# proto.net
KiCad netlist of a schematic drawn in EAGLE
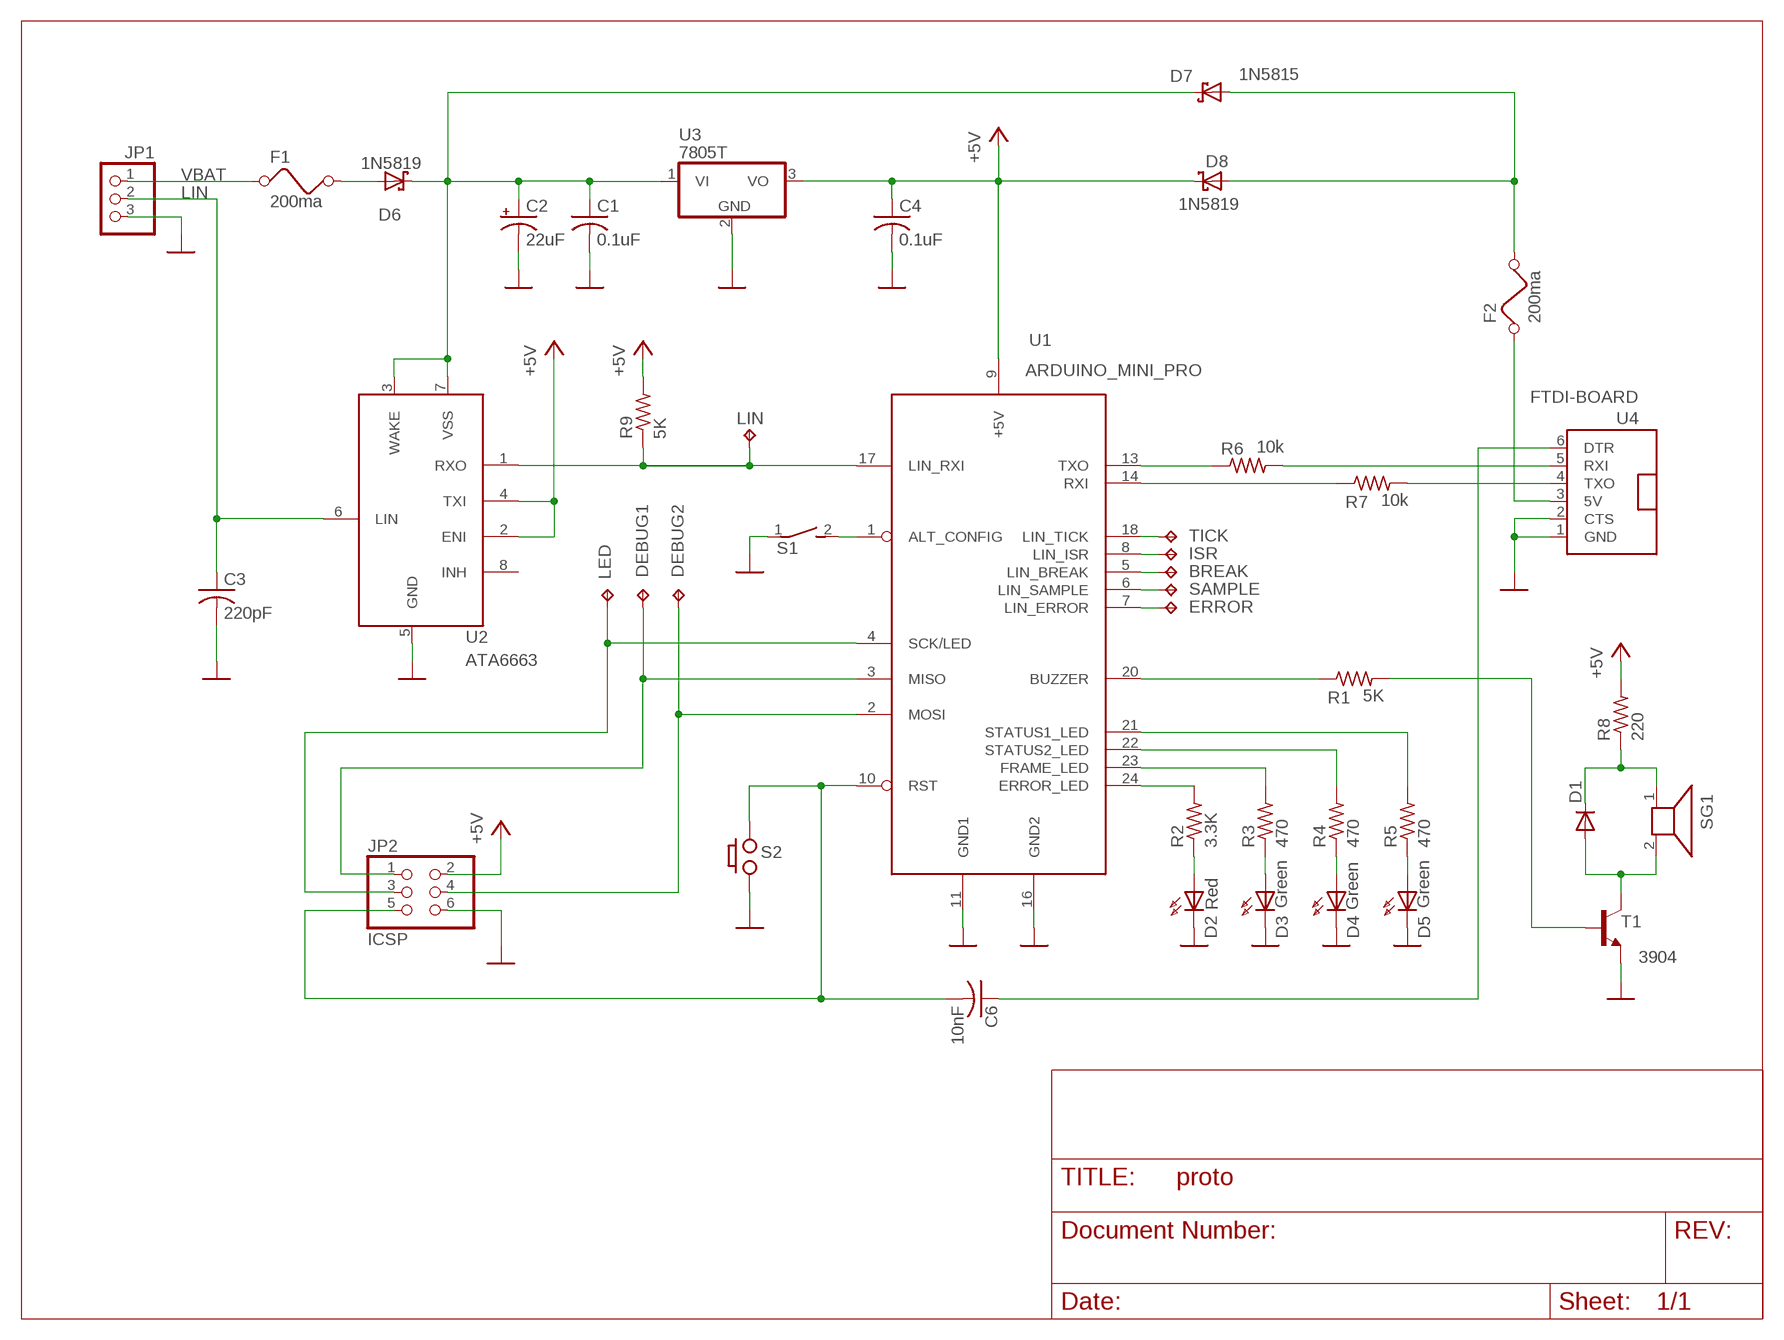
[diagram p0: schematic, sheet 1]

(export (version "E")
  (design (tool "Eeschema 10.0.6"))
  (components
    (comp (ref "BREAK")
      (value "TPPAD1-17")
      (footprint "eagle-import:P1-17")
      (libsource (lib "eagle-import") (part "TPPAD1-17"))
    )
    (comp (ref "C1")
      (value "0.1uF")
      (footprint "eagle-import:C0805")
      (libsource (lib "eagle-import") (part "C-USC0805"))
    )
    (comp (ref "C2")
      (value "22uF")
      (footprint "eagle-import:SMC_C")
      (libsource (lib "eagle-import") (part "CPOL-USSMCC"))
    )
    (comp (ref "C3")
      (value "220pF")
      (footprint "eagle-import:C0805")
      (libsource (lib "eagle-import") (part "C-USC0805"))
    )
    (comp (ref "C4")
      (value "0.1uF")
      (footprint "eagle-import:C0805")
      (libsource (lib "eagle-import") (part "C-USC0805"))
    )
    (comp (ref "C6")
      (value "10nF")
      (footprint "eagle-import:C0805")
      (libsource (lib "eagle-import") (part "C-USC0805"))
    )
    (comp (ref "D1")
      (value "DIODE-MINIMELF")
      (footprint "eagle-import:MINIMELF")
      (libsource (lib "eagle-import") (part "DIODE-MINIMELF"))
    )
    (comp (ref "D2")
      (value "Red")
      (footprint "eagle-import:HLMP6")
      (fields (field (name "MF") "AGILENT TECHNOLOGIES") (field (name "MPN") "HLMP-6500"))
      (libsource (lib "eagle-import") (part "HLMP6"))
    )
    (comp (ref "D3")
      (value "Green")
      (footprint "eagle-import:HLMP6")
      (fields (field (name "MF") "AGILENT TECHNOLOGIES") (field (name "MPN") "HLMP-6500"))
      (libsource (lib "eagle-import") (part "HLMP6"))
    )
    (comp (ref "D4")
      (value "Green")
      (footprint "eagle-import:HLMP6")
      (fields (field (name "MF") "AGILENT TECHNOLOGIES") (field (name "MPN") "HLMP-6500"))
      (libsource (lib "eagle-import") (part "HLMP6"))
    )
    (comp (ref "D5")
      (value "Green")
      (footprint "eagle-import:HLMP6")
      (fields (field (name "MF") "AGILENT TECHNOLOGIES") (field (name "MPN") "HLMP-6500"))
      (libsource (lib "eagle-import") (part "HLMP6"))
    )
    (comp (ref "D6")
      (value "1N5819")
      (footprint "eagle-import:SMC")
      (libsource (lib "eagle-import") (part "MBRS30T32"))
    )
    (comp (ref "D7")
      (value "1N5815")
      (footprint "eagle-import:SMC")
      (libsource (lib "eagle-import") (part "MBRS30T32"))
    )
    (comp (ref "D8")
      (value "1N5819")
      (footprint "eagle-import:SMC")
      (libsource (lib "eagle-import") (part "MBRS30T32"))
    )
    (comp (ref "DEBUG1")
      (value "TPPAD1-17")
      (footprint "eagle-import:P1-17")
      (libsource (lib "eagle-import") (part "TPPAD1-17"))
    )
    (comp (ref "DEBUG2")
      (value "TPPAD1-17")
      (footprint "eagle-import:P1-17")
      (libsource (lib "eagle-import") (part "TPPAD1-17"))
    )
    (comp (ref "ERROR")
      (value "TPPAD1-17")
      (footprint "eagle-import:P1-17")
      (libsource (lib "eagle-import") (part "TPPAD1-17"))
    )
    (comp (ref "F1")
      (value "200ma")
      (footprint "eagle-import:FUSE")
      (libsource (lib "eagle-import") (part "FUSE"))
    )
    (comp (ref "F2")
      (value "200ma")
      (footprint "eagle-import:FUSE")
      (libsource (lib "eagle-import") (part "FUSE"))
    )
    (comp (ref "ISR")
      (value "TPPAD1-17")
      (footprint "eagle-import:P1-17")
      (libsource (lib "eagle-import") (part "TPPAD1-17"))
    )
    (comp (ref "JP1")
      (value "PINHD-1X3")
      (footprint "eagle-import:1X03")
      (libsource (lib "eagle-import") (part "PINHD-1X3"))
    )
    (comp (ref "JP2")
      (value "ICSP")
      (footprint "eagle-import:2X03")
      (libsource (lib "eagle-import") (part "PINHD-2X3"))
    )
    (comp (ref "LED")
      (value "TPPAD1-17")
      (footprint "eagle-import:P1-17")
      (libsource (lib "eagle-import") (part "TPPAD1-17"))
    )
    (comp (ref "LIN")
      (value "TPPAD1-17")
      (footprint "eagle-import:P1-17")
      (libsource (lib "eagle-import") (part "TPPAD1-17"))
    )
    (comp (ref "R1")
      (value "5K")
      (footprint "eagle-import:R0805")
      (libsource (lib "eagle-import") (part "R-US_R0805"))
    )
    (comp (ref "R2")
      (value "3.3K")
      (footprint "eagle-import:R0805")
      (libsource (lib "eagle-import") (part "R-US_R0805"))
    )
    (comp (ref "R3")
      (value "470")
      (footprint "eagle-import:R0805")
      (libsource (lib "eagle-import") (part "R-US_R0805"))
    )
    (comp (ref "R4")
      (value "470")
      (footprint "eagle-import:R0805")
      (libsource (lib "eagle-import") (part "R-US_R0805"))
    )
    (comp (ref "R5")
      (value "470")
      (footprint "eagle-import:R0805")
      (libsource (lib "eagle-import") (part "R-US_R0805"))
    )
    (comp (ref "R6")
      (value "10k")
      (footprint "eagle-import:R0805")
      (libsource (lib "eagle-import") (part "R-US_R0805"))
    )
    (comp (ref "R7")
      (value "10k")
      (footprint "eagle-import:R0805")
      (libsource (lib "eagle-import") (part "R-US_R0805"))
    )
    (comp (ref "R8")
      (value "220")
      (footprint "eagle-import:R0805")
      (libsource (lib "eagle-import") (part "R-US_R0805"))
    )
    (comp (ref "R9")
      (value "5K")
      (footprint "eagle-import:R0805")
      (libsource (lib "eagle-import") (part "R-US_R0805"))
    )
    (comp (ref "S1")
      (value "DS01E")
      (footprint "eagle-import:DS-01")
      (libsource (lib "eagle-import") (part "DS01E"))
    )
    (comp (ref "S2")
      (value "PUSH_BUTTON")
      (footprint "eagle-import:DUMMY-2")
      (libsource (lib "eagle-import") (part "PUSH_BUTTON"))
    )
    (comp (ref "SAMPLE")
      (value "TPPAD1-17")
      (footprint "eagle-import:P1-17")
      (libsource (lib "eagle-import") (part "TPPAD1-17"))
    )
    (comp (ref "SG1")
      (value "F/SMX")
      (footprint "eagle-import:F_SMX")
      (libsource (lib "eagle-import") (part "F/SMX"))
    )
    (comp (ref "T1")
      (value "3904")
      (footprint "eagle-import:SOT23-BEC")
      (libsource (lib "eagle-import") (part "-NPN-SOT23-BECMMBT3904LT1"))
    )
    (comp (ref "TICK")
      (value "TPPAD1-17")
      (footprint "eagle-import:P1-17")
      (libsource (lib "eagle-import") (part "TPPAD1-17"))
    )
    (comp (ref "U1")
      (value "ARDUINO_MINI_PRO")
      (footprint "eagle-import:ARDUINO-PRO-MINI")
      (libsource (lib "eagle-import") (part "ARDUINO_MINI_PRODIP24-6"))
    )
    (comp (ref "U2")
      (value "ATA6663")
      (footprint "eagle-import:SO-08")
      (libsource (lib "eagle-import") (part "ATA6663"))
    )
    (comp (ref "U3")
      (value "7805T")
      (footprint "eagle-import:TO220H")
      (libsource (lib "eagle-import") (part "78T05"))
    )
    (comp (ref "U4")
      (value "FTDI-BOARD")
      (footprint "eagle-import:FTDI-BOARD")
      (libsource (lib "eagle-import") (part "FTDI-OBARD"))
    )
  )
  (nets
    (net (code "1") (name "+5V") (class "Default")
      (node (ref "C4") (pin "1") (pinfunction "1_1") (pintype "passive"))
      (node (ref "D8") (pin "C") (pinfunction "C_C") (pintype "passive"))
      (node (ref "JP2") (pin "2") (pinfunction "2_2") (pintype "passive"))
      (node (ref "R8") (pin "2") (pinfunction "2_2") (pintype "passive"))
      (node (ref "R9") (pin "2") (pinfunction "2_2") (pintype "passive"))
      (node (ref "U1") (pin "9") (pinfunction "+5V_9") (pintype "power_in"))
      (node (ref "U2") (pin "2") (pinfunction "ENI_2") (pintype "input"))
      (node (ref "U2") (pin "4") (pinfunction "TXI_4") (pintype "input"))
      (node (ref "U3") (pin "3") (pinfunction "VO_3") (pintype "passive"))
    )
    (net (code "2") (name "/LIN") (class "Default")
      (node (ref "C3") (pin "1") (pinfunction "1_1") (pintype "passive"))
      (node (ref "JP1") (pin "2") (pinfunction "2_2") (pintype "passive"))
      (node (ref "U2") (pin "6") (pinfunction "LIN_6") (pintype "bidirectional"))
    )
    (net (code "3") (name "/VBAT") (class "Default")
      (node (ref "F1") (pin "1") (pinfunction "1_1") (pintype "passive"))
      (node (ref "JP1") (pin "1") (pinfunction "1_1") (pintype "passive"))
    )
    (net (code "4") (name "GND") (class "Default")
      (node (ref "C1") (pin "2") (pinfunction "2_2") (pintype "passive"))
      (node (ref "C2") (pin "-") (pinfunction "-_-") (pintype "passive"))
      (node (ref "C3") (pin "2") (pinfunction "2_2") (pintype "passive"))
      (node (ref "C4") (pin "2") (pinfunction "2_2") (pintype "passive"))
      (node (ref "D2") (pin "K") (pinfunction "K_K") (pintype "passive"))
      (node (ref "D3") (pin "K") (pinfunction "K_K") (pintype "passive"))
      (node (ref "D4") (pin "K") (pinfunction "K_K") (pintype "passive"))
      (node (ref "D5") (pin "K") (pinfunction "K_K") (pintype "passive"))
      (node (ref "JP1") (pin "3") (pinfunction "3_3") (pintype "passive"))
      (node (ref "JP2") (pin "6") (pinfunction "6_6") (pintype "passive"))
      (node (ref "S1") (pin "1") (pinfunction "1_1") (pintype "passive"))
      (node (ref "S2") (pin "P$2") (pinfunction "P$4_P$2") (pintype "passive"))
      (node (ref "T1") (pin "E") (pinfunction "E_E") (pintype "passive"))
      (node (ref "U1") (pin "11") (pinfunction "GND1_11") (pintype "power_in"))
      (node (ref "U1") (pin "16") (pinfunction "GND2_16") (pintype "power_in"))
      (node (ref "U2") (pin "5") (pinfunction "GND_5") (pintype "power_in"))
      (node (ref "U3") (pin "2") (pinfunction "GND_2") (pintype "passive"))
      (node (ref "U4") (pin "1") (pinfunction "GND_1") (pintype "power_in"))
      (node (ref "U4") (pin "2") (pinfunction "CTS_2") (pintype "input"))
    )
    (net (code "5") (name "Net-(D1-PadA)") (class "Default")
      (node (ref "D1") (pin "A") (pinfunction "A_A") (pintype "passive"))
      (node (ref "SG1") (pin "2") (pinfunction "2_2") (pintype "passive"))
      (node (ref "T1") (pin "C") (pinfunction "C_C") (pintype "passive"))
    )
    (net (code "6") (name "Net-(D1-PadC)") (class "Default")
      (node (ref "D1") (pin "C") (pinfunction "C_C") (pintype "passive"))
      (node (ref "R8") (pin "1") (pinfunction "1_1") (pintype "passive"))
      (node (ref "SG1") (pin "1") (pinfunction "1_1") (pintype "passive"))
    )
    (net (code "7") (name "Net-(D2-PadA)") (class "Default")
      (node (ref "D2") (pin "A") (pinfunction "A_A") (pintype "passive"))
      (node (ref "R2") (pin "1") (pinfunction "1_1") (pintype "passive"))
    )
    (net (code "8") (name "Net-(D3-PadA)") (class "Default")
      (node (ref "D3") (pin "A") (pinfunction "A_A") (pintype "passive"))
      (node (ref "R3") (pin "1") (pinfunction "1_1") (pintype "passive"))
    )
    (net (code "9") (name "Net-(D4-PadA)") (class "Default")
      (node (ref "D4") (pin "A") (pinfunction "A_A") (pintype "passive"))
      (node (ref "R4") (pin "1") (pinfunction "1_1") (pintype "passive"))
    )
    (net (code "10") (name "Net-(D5-PadA)") (class "Default")
      (node (ref "D5") (pin "A") (pinfunction "A_A") (pintype "passive"))
      (node (ref "R5") (pin "1") (pinfunction "1_1") (pintype "passive"))
    )
    (net (code "11") (name "Net-(D6-PadA)") (class "Default")
      (node (ref "D6") (pin "A") (pinfunction "A_A") (pintype "passive"))
      (node (ref "F1") (pin "2") (pinfunction "2_2") (pintype "passive"))
    )
    (net (code "12") (name "Net-(D7-PadA)") (class "Default")
      (node (ref "D7") (pin "A") (pinfunction "A_A") (pintype "passive"))
      (node (ref "D8") (pin "A") (pinfunction "A_A") (pintype "passive"))
      (node (ref "F2") (pin "2") (pinfunction "2_2") (pintype "passive"))
    )
    (net (code "13") (name "Net-(R1-Pad2)") (class "Default")
      (node (ref "R1") (pin "2") (pinfunction "2_2") (pintype "passive"))
      (node (ref "T1") (pin "B") (pinfunction "B_B") (pintype "passive"))
    )
    (net (code "14") (name "Net-(S2-P$3)") (class "Default")
      (node (ref "C6") (pin "2") (pinfunction "2_2") (pintype "passive"))
      (node (ref "JP2") (pin "5") (pinfunction "5_5") (pintype "passive"))
      (node (ref "S2") (pin "P$1") (pinfunction "P$3_P$1") (pintype "passive"))
      (node (ref "U1") (pin "10") (pinfunction "RST_10") (pintype "input"))
    )
    (net (code "15") (name "Net-(U1-ALT_CONFIG)") (class "Default")
      (node (ref "S1") (pin "2") (pinfunction "2_2") (pintype "passive"))
      (node (ref "U1") (pin "1") (pinfunction "ALT_CONFIG_1") (pintype "input"))
    )
    (net (code "16") (name "Net-(U1-BUZZER)") (class "Default")
      (node (ref "R1") (pin "1") (pinfunction "1_1") (pintype "passive"))
      (node (ref "U1") (pin "20") (pinfunction "BUZZER_20") (pintype "output"))
    )
    (net (code "17") (name "Net-(U1-ERROR_LED)") (class "Default")
      (node (ref "R2") (pin "2") (pinfunction "2_2") (pintype "passive"))
      (node (ref "U1") (pin "24") (pinfunction "ERROR_LED_24") (pintype "output"))
    )
    (net (code "18") (name "Net-(U1-FRAME_LED)") (class "Default")
      (node (ref "R3") (pin "2") (pinfunction "2_2") (pintype "passive"))
      (node (ref "U1") (pin "23") (pinfunction "FRAME_LED_23") (pintype "output"))
    )
    (net (code "19") (name "Net-(U1-LIN_BREAK)") (class "Default")
      (node (ref "BREAK") (pin "TP") (pinfunction "TP_TP") (pintype "input"))
      (node (ref "U1") (pin "5") (pinfunction "LIN_BREAK_5") (pintype "output"))
    )
    (net (code "20") (name "Net-(U1-LIN_ERROR)") (class "Default")
      (node (ref "ERROR") (pin "TP") (pinfunction "TP_TP") (pintype "input"))
      (node (ref "U1") (pin "7") (pinfunction "LIN_ERROR_7") (pintype "output"))
    )
    (net (code "21") (name "Net-(U1-LIN_ISR)") (class "Default")
      (node (ref "ISR") (pin "TP") (pinfunction "TP_TP") (pintype "input"))
      (node (ref "U1") (pin "8") (pinfunction "LIN_ISR_8") (pintype "output"))
    )
    (net (code "22") (name "Net-(U1-LIN_RXI)") (class "Default")
      (node (ref "LIN") (pin "TP") (pinfunction "TP_TP") (pintype "input"))
      (node (ref "R9") (pin "1") (pinfunction "1_1") (pintype "passive"))
      (node (ref "U1") (pin "17") (pinfunction "LIN_RXI_17") (pintype "input"))
      (node (ref "U2") (pin "1") (pinfunction "RXO_1") (pintype "output"))
    )
    (net (code "23") (name "Net-(U1-LIN_SAMPLE)") (class "Default")
      (node (ref "SAMPLE") (pin "TP") (pinfunction "TP_TP") (pintype "input"))
      (node (ref "U1") (pin "6") (pinfunction "LIN_SAMPLE_6") (pintype "output"))
    )
    (net (code "24") (name "Net-(U1-LIN_TICK)") (class "Default")
      (node (ref "TICK") (pin "TP") (pinfunction "TP_TP") (pintype "input"))
      (node (ref "U1") (pin "18") (pinfunction "LIN_TICK_18") (pintype "output"))
    )
    (net (code "25") (name "Net-(U1-MISO)") (class "Default")
      (node (ref "DEBUG1") (pin "TP") (pinfunction "TP_TP") (pintype "input"))
      (node (ref "JP2") (pin "1") (pinfunction "1_1") (pintype "passive"))
      (node (ref "U1") (pin "3") (pinfunction "MISO_3") (pintype "input"))
    )
    (net (code "26") (name "Net-(U1-MOSI)") (class "Default")
      (node (ref "DEBUG2") (pin "TP") (pinfunction "TP_TP") (pintype "input"))
      (node (ref "JP2") (pin "4") (pinfunction "4_4") (pintype "passive"))
      (node (ref "U1") (pin "2") (pinfunction "MOSI_2") (pintype "input"))
    )
    (net (code "27") (name "Net-(U1-RXI)") (class "Default")
      (node (ref "R7") (pin "1") (pinfunction "1_1") (pintype "passive"))
      (node (ref "U1") (pin "14") (pinfunction "RXI_14") (pintype "output"))
    )
    (net (code "28") (name "Net-(U1-SCK{slash}LED)") (class "Default")
      (node (ref "JP2") (pin "3") (pinfunction "3_3") (pintype "passive"))
      (node (ref "LED") (pin "TP") (pinfunction "TP_TP") (pintype "input"))
      (node (ref "U1") (pin "4") (pinfunction "SCK/LED_4") (pintype "output"))
    )
    (net (code "29") (name "Net-(U1-STATUS1_LED)") (class "Default")
      (node (ref "R5") (pin "2") (pinfunction "2_2") (pintype "passive"))
      (node (ref "U1") (pin "21") (pinfunction "STATUS1_LED_21") (pintype "output"))
    )
    (net (code "30") (name "Net-(U1-STATUS2_LED)") (class "Default")
      (node (ref "R4") (pin "2") (pinfunction "2_2") (pintype "passive"))
      (node (ref "U1") (pin "22") (pinfunction "STATUS2_LED_22") (pintype "output"))
    )
    (net (code "31") (name "Net-(U1-TXO)") (class "Default")
      (node (ref "R6") (pin "1") (pinfunction "1_1") (pintype "passive"))
      (node (ref "U1") (pin "13") (pinfunction "TXO_13") (pintype "input"))
    )
    (net (code "32") (name "Net-(U2-VSS)") (class "Default")
      (node (ref "C1") (pin "1") (pinfunction "1_1") (pintype "passive"))
      (node (ref "C2") (pin "+") (pinfunction "+_+") (pintype "passive"))
      (node (ref "D6") (pin "C") (pinfunction "C_C") (pintype "passive"))
      (node (ref "D7") (pin "C") (pinfunction "C_C") (pintype "passive"))
      (node (ref "U2") (pin "3") (pinfunction "WAKE_3") (pintype "bidirectional"))
      (node (ref "U2") (pin "7") (pinfunction "VSS_7") (pintype "power_in"))
      (node (ref "U3") (pin "1") (pinfunction "VI_1") (pintype "input"))
    )
    (net (code "33") (name "Net-(U4-5V)") (class "Default")
      (node (ref "F2") (pin "1") (pinfunction "1_1") (pintype "passive"))
      (node (ref "U4") (pin "3") (pinfunction "5V_3") (pintype "power_in"))
    )
    (net (code "34") (name "Net-(U4-DTR)") (class "Default")
      (node (ref "C6") (pin "1") (pinfunction "1_1") (pintype "passive"))
      (node (ref "U4") (pin "6") (pinfunction "DTR_6") (pintype "output"))
    )
    (net (code "35") (name "Net-(U4-RXI)") (class "Default")
      (node (ref "R6") (pin "2") (pinfunction "2_2") (pintype "passive"))
      (node (ref "U4") (pin "5") (pinfunction "RXI_5") (pintype "input"))
    )
    (net (code "36") (name "Net-(U4-TXO)") (class "Default")
      (node (ref "R7") (pin "2") (pinfunction "2_2") (pintype "passive"))
      (node (ref "U4") (pin "4") (pinfunction "TXO_4") (pintype "output"))
    )
    (net (code "37") (name "unconnected-(U2-INH-Pad8)") (class "Default")
      (node (ref "U2") (pin "8") (pinfunction "INH_8") (pintype "output"))
    )
  )
)
